# LPC1769.net
KiCad netlist of a schematic drawn in Altium Designer
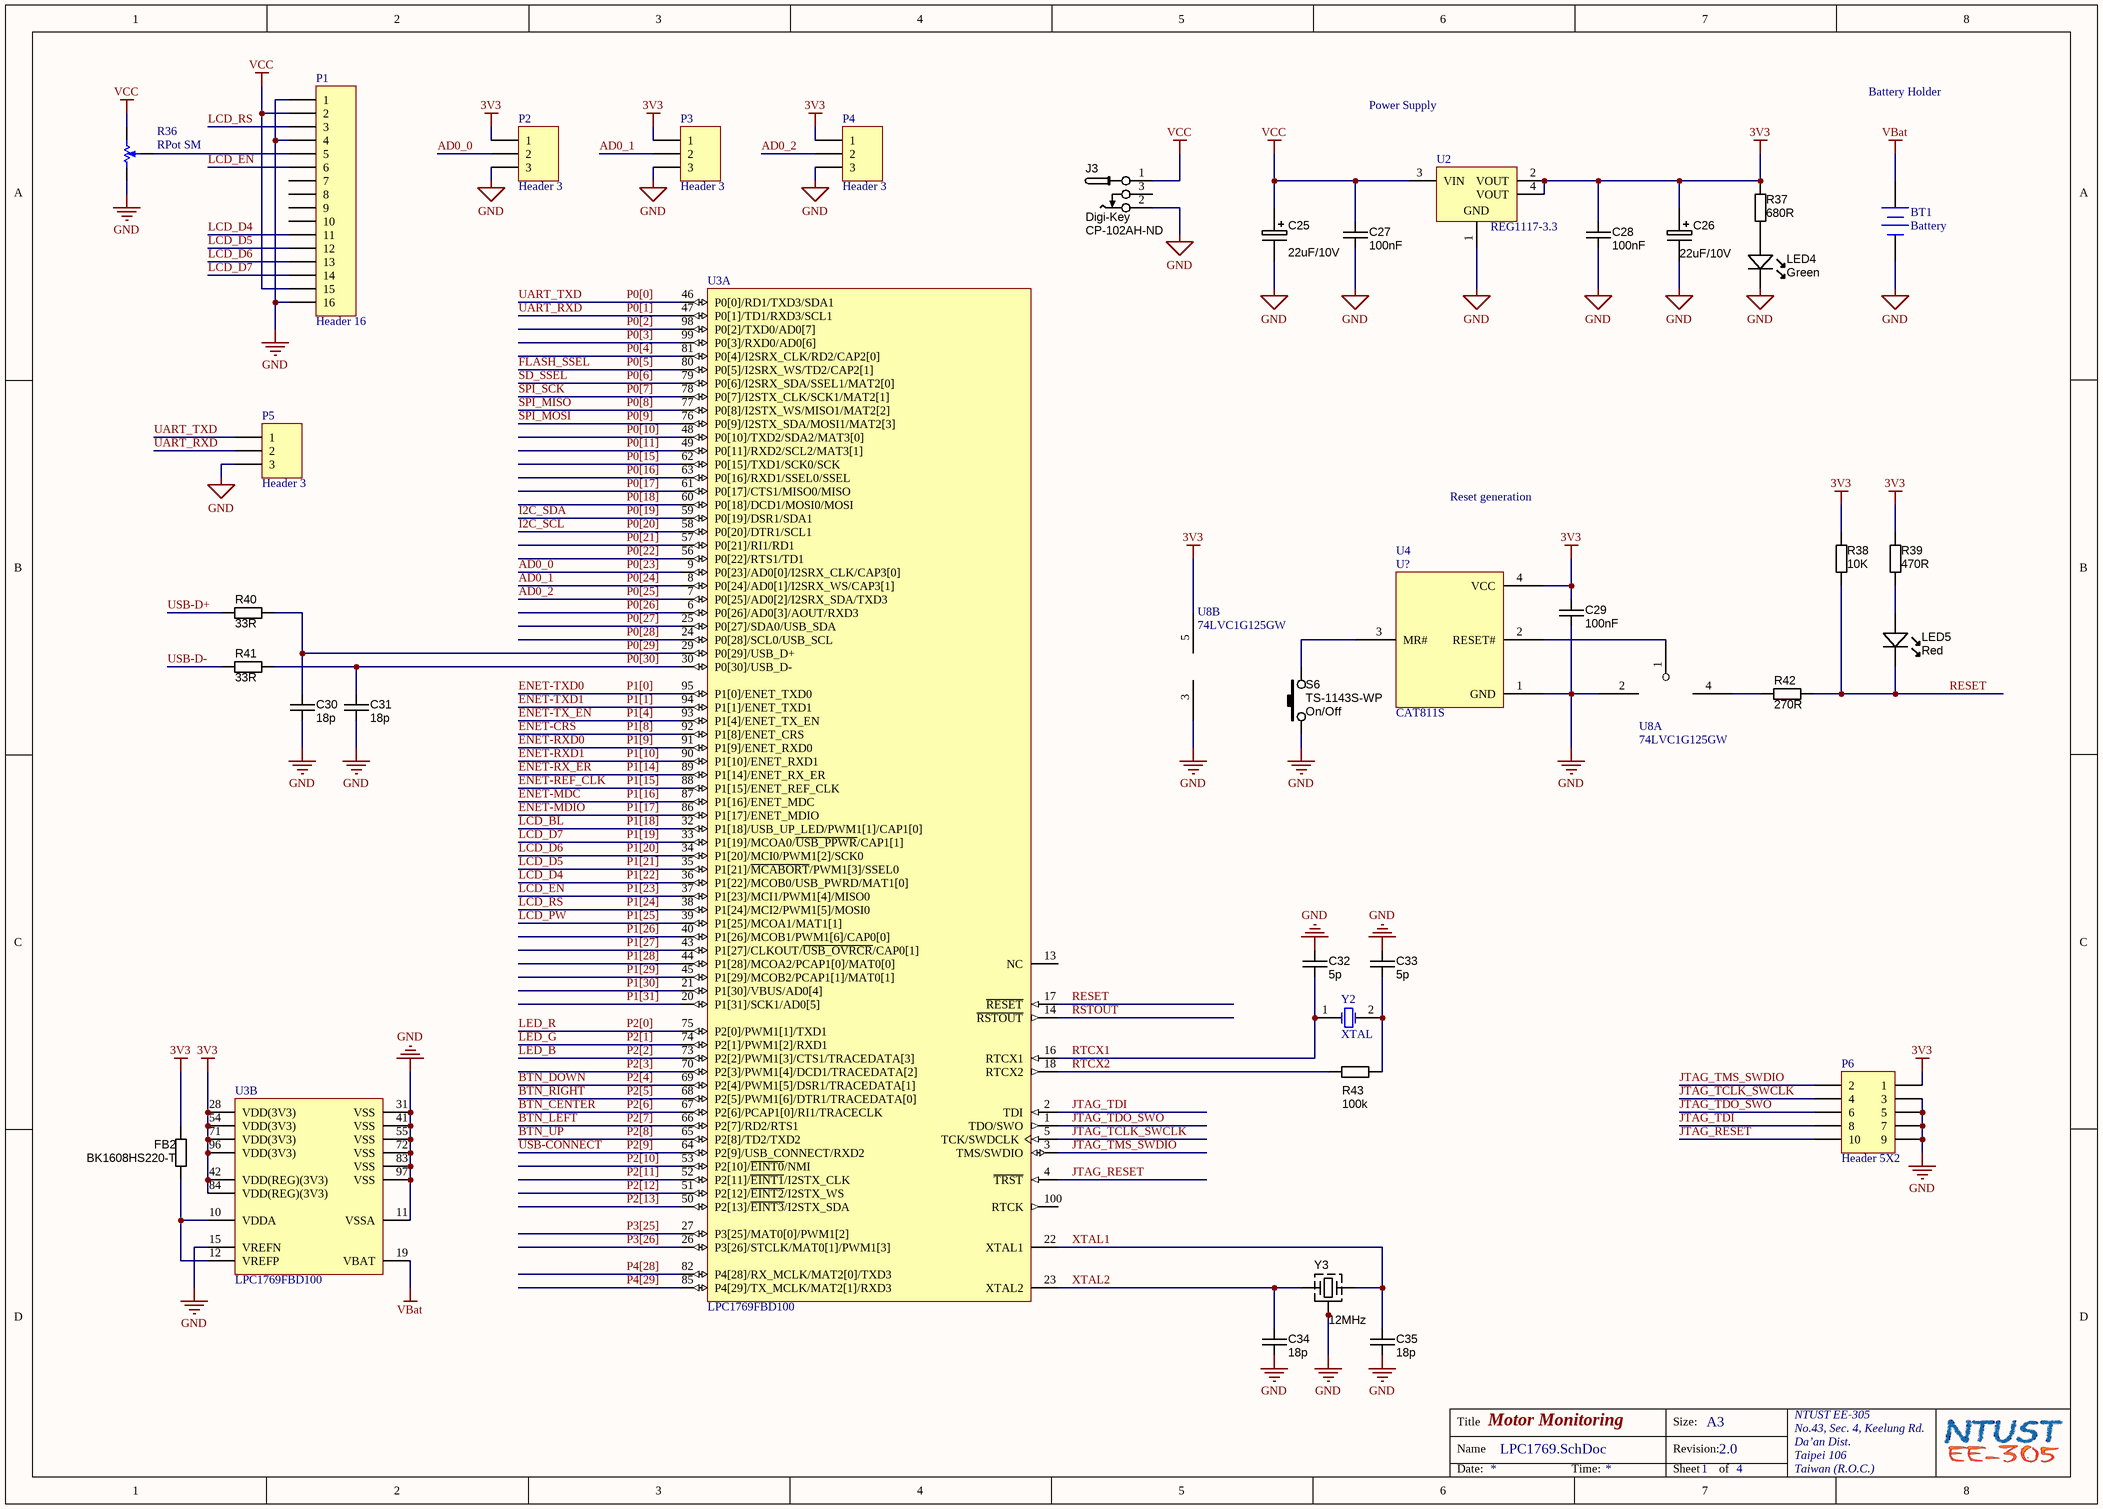
[diagram p0: LPC1769.SchDoc]

(export (version "E")
  (design (tool "Eeschema 10.0.6"))
  (components
    (comp (ref "BT1")
      (value "Battery")
      (footprint "BAT-2")
      (description "Multicell Battery")
      (fields (field (name "PUBLISHER") "Altium Limited"))
      (libsource (lib "Miscellaneous Devices") (part "Battery"))
    )
    (comp (ref "C25")
      (value "~")
      (footprint "CAP_ELEC_5x5.7")
      (description "Capacitor SMD Tantalum 100uF 20% 6.3V 1210")
      (fields (field (name "TOLERANCE") "?0%") (field (name "ALTIUM_UNNAMED_1") "22uF/10V"))
      (libsource (lib "PBL - Capacitors") (part "CAPT_100u_1210_6V3"))
    )
    (comp (ref "C26")
      (value "~")
      (footprint "CAP_ELEC_5x5.7")
      (description "Capacitor SMD Tantalum 100uF 20% 6.3V 1210")
      (fields (field (name "TOLERANCE") "?0%") (field (name "ALTIUM_UNNAMED_1") "22uF/10V"))
      (libsource (lib "PBL - Capacitors") (part "CAPT_100u_1210_6V3"))
    )
    (comp (ref "C27")
      (value "100nF")
      (footprint "CAPC1608N")
      (description "Capacitor SMD Cer 100nF 10% 50V X7R 0805")
      (fields (field (name "TOLERANCE") "?0%") (field (name "Comment") "approved sub OK"))
      (libsource (lib "PBL - Capacitors") (part "CAPC_100n_0805"))
    )
    (comp (ref "C28")
      (value "100nF")
      (footprint "CAPC1608N")
      (description "Capacitor SMD Cer 100nF 10% 50V X7R 0805")
      (fields (field (name "TOLERANCE") "?0%") (field (name "Comment") "approved sub OK"))
      (libsource (lib "PBL - Capacitors") (part "CAPC_100n_0805"))
    )
    (comp (ref "C29")
      (value "100nF")
      (footprint "CAPC1005N")
      (description "Capacitor SMD Cer 100nF 10% 50V X7R 0805")
      (fields (field (name "TOLERANCE") "?0%") (field (name "Comment") "approved sub OK"))
      (libsource (lib "PBL - Capacitors") (part "CAPC_100n_0805"))
    )
    (comp (ref "C30")
      (value "18p")
      (footprint "CAPC1608N")
      (description "Capacitor SMD Cer 100nF 10% 50V X7R 0805")
      (fields (field (name "TOLERANCE") "?0%") (field (name "Comment") "approved sub OK"))
      (libsource (lib "PBL - Capacitors") (part "CAPC_100n_0805"))
    )
    (comp (ref "C31")
      (value "18p")
      (footprint "CAPC1608N")
      (description "Capacitor SMD Cer 100nF 10% 50V X7R 0805")
      (fields (field (name "TOLERANCE") "?0%") (field (name "Comment") "approved sub OK"))
      (libsource (lib "PBL - Capacitors") (part "CAPC_100n_0805"))
    )
    (comp (ref "C32")
      (value "5p")
      (footprint "CAPC1005N")
      (description "Capacitor SMD Cer 100nF 10% 50V X7R 0805")
      (fields (field (name "TOLERANCE") "?0%") (field (name "Comment") "approved sub OK"))
      (libsource (lib "PBL - Capacitors") (part "CAPC_100n_0805"))
    )
    (comp (ref "C33")
      (value "5p")
      (footprint "CAPC1005N")
      (description "Capacitor SMD Cer 100nF 10% 50V X7R 0805")
      (fields (field (name "TOLERANCE") "?0%") (field (name "Comment") "approved sub OK"))
      (libsource (lib "PBL - Capacitors") (part "CAPC_100n_0805"))
    )
    (comp (ref "C34")
      (value "18p")
      (footprint "CAPC1005N")
      (description "Capacitor SMD Cer 100nF 10% 50V X7R 0805")
      (fields (field (name "TOLERANCE") "?0%") (field (name "Comment") "approved sub OK"))
      (libsource (lib "PBL - Capacitors") (part "CAPC_100n_0805"))
    )
    (comp (ref "C35")
      (value "18p")
      (footprint "CAPC1005N")
      (description "Capacitor SMD Cer 100nF 10% 50V X7R 0805")
      (fields (field (name "TOLERANCE") "?0%") (field (name "Comment") "approved sub OK"))
      (libsource (lib "PBL - Capacitors") (part "CAPC_100n_0805"))
    )
    (comp (ref "FB2")
      (value "BK1608HS220-T")
      (footprint "RESC2012N")
      (description "Resistor SMD chip 10k Ohm 0.125W 5% 0805")
      (fields (field (name "TOLERANCE") "?%") (field (name "Comment") "Thick Film"))
      (libsource (lib "") (part "RES_10K_0805_5%_1"))
    )
    (comp (ref "J3")
      (value "CONN_PWR_JACK_2.1x5.5mm")
      (footprint "CONN_PWR_JACK_2.1x5.5mm")
      (description "Power Connector, THT, 2.1mm ID, 5.5mm OD")
      (fields (field (name "SUPPLIER 1") "Digi-Key") (field (name "SUPPLIER PART NUMBER 1") "CP-102AH-ND"))
      (libsource (lib "PBL - Connectors") (part "CONN_PWR_JACK_2.1x5.5mm"))
    )
    (comp (ref "LED4")
      (value "Green")
      (footprint "LED-0603-GREEN")
      (description "LED, 0805 SMD, Green")
      (libsource (lib "PBL - Light Sources") (part "LED_SMD_Green_0805_8mcd"))
    )
    (comp (ref "LED5")
      (value "Red")
      (footprint "LED-0603-GREEN")
      (description "LED, 0805 SMD, Red")
      (libsource (lib "PBL - Light Sources") (part "LED_SMD_Red_0805"))
    )
    (comp (ref "P1")
      (value "Header 16")
      (footprint "HDR1X16")
      (description "Header, 16-Pin")
      (fields (field (name "PUBLISHER") "Altium Limited"))
      (libsource (lib "Miscellaneous Connectors") (part "Header 16"))
    )
    (comp (ref "P2")
      (value "Header 3")
      (footprint "HDR1X3")
      (description "Header, 3-Pin")
      (fields (field (name "PUBLISHER") "Altium Limited"))
      (libsource (lib "Miscellaneous Connectors") (part "Header 3"))
    )
    (comp (ref "P3")
      (value "Header 3")
      (footprint "HDR1X3")
      (description "Header, 3-Pin")
      (fields (field (name "PUBLISHER") "Altium Limited"))
      (libsource (lib "Miscellaneous Connectors") (part "Header 3"))
    )
    (comp (ref "P4")
      (value "Header 3")
      (footprint "HDR1X3")
      (description "Header, 3-Pin")
      (fields (field (name "PUBLISHER") "Altium Limited"))
      (libsource (lib "Miscellaneous Connectors") (part "Header 3"))
    )
    (comp (ref "P5")
      (value "Header 3")
      (footprint "HDR1X3")
      (description "Header, 3-Pin")
      (fields (field (name "PUBLISHER") "Altium Limited"))
      (libsource (lib "Miscellaneous Connectors") (part "Header 3"))
    )
    (comp (ref "P6")
      (value "Header 5X2")
      (footprint "Header 5x2p")
      (description "Header, 5-Pin, Dual row")
      (fields (field (name "PUBLISHER") "Altium Limited"))
      (libsource (lib "Miscellaneous Connectors") (part "Header 5X2"))
    )
    (comp (ref "R36")
      (value "RPot SM")
      (footprint "POT4MM-2")
      (description "Square Trimming Potentiometer")
      (fields (field (name "PUBLISHER") "Altium Limited"))
      (libsource (lib "Miscellaneous Devices") (part "RPot SM"))
    )
    (comp (ref "R37")
      (value "680R")
      (footprint "RESC1005N")
      (description "Resistor SMD chip 330 Ohm 0.063W 5% 0402")
      (fields (field (name "TOLERANCE") "?%") (field (name "Comment") "Thick Film"))
      (libsource (lib "") (part "RES_330R_0402_5%_1"))
    )
    (comp (ref "R38")
      (value "10K")
      (footprint "RESC1005N")
      (description "Resistor SMD chip 10k Ohm 0.125W 5% 0805")
      (fields (field (name "TOLERANCE") "?%") (field (name "Comment") "Thick Film"))
      (libsource (lib "") (part "RES_10K_0805_5%_1"))
    )
    (comp (ref "R39")
      (value "470R")
      (footprint "RESC1005N")
      (description "Resistor SMD chip 470 Ohm 0.1W 5% 0603")
      (fields (field (name "TOLERANCE") "?%") (field (name "Comment") "Thick Film"))
      (libsource (lib "PBL - Resistors") (part "RES_470R_0603_5%"))
    )
    (comp (ref "R40")
      (value "33R")
      (footprint "RESC1608N")
      (description "Resistor SMD chip 10k Ohm 0.125W 5% 0805")
      (fields (field (name "TOLERANCE") "?%") (field (name "Comment") "Thick Film"))
      (libsource (lib "PBL - Resistors") (part "RES_10K_0805_5%"))
    )
    (comp (ref "R41")
      (value "33R")
      (footprint "RESC1608N")
      (description "Resistor SMD chip 10k Ohm 0.125W 5% 0805")
      (fields (field (name "TOLERANCE") "?%") (field (name "Comment") "Thick Film"))
      (libsource (lib "PBL - Resistors") (part "RES_10K_0805_5%"))
    )
    (comp (ref "R42")
      (value "270R")
      (footprint "RESC1005N")
      (description "Resistor SMD chip 330 Ohm 0.063W 5% 0402")
      (fields (field (name "TOLERANCE") "?%") (field (name "Comment") "Thick Film"))
      (libsource (lib "PBL - Resistors") (part "RES_330R_0402_5%"))
    )
    (comp (ref "R43")
      (value "100k")
      (footprint "RESC1005N")
      (description "Resistor SMD chip 10k Ohm 0.125W 5% 0805")
      (fields (field (name "TOLERANCE") "?%") (field (name "Comment") "Thick Film"))
      (libsource (lib "PBL - Resistors") (part "RES_10K_0805_5%"))
    )
    (comp (ref "S6")
      (value "TS-1143S-WP")
      (footprint "TS-1143S")
      (description "Switch SMD Tact 4.3mm Stem")
      (fields (field (name "FUNCTION") "On/Off"))
      (libsource (lib "PBL - Switches") (part "SW_SMD_PB_4.3mm"))
    )
    (comp (ref "U2")
      (value "REG1117-3.3")
      (footprint "TI-DCY4_N")
      (fields (field (name "MANUFACTURER") "Texas Instruments"))
      (libsource (lib "TI Power Management Linear Regulator Single Channel LDO (400-7500mA)") (part "REG1117-3.3"))
    )
    (comp (ref "U3")
      (value "LPC1769FBD100")
      (footprint "SOT407-1_V")
      (libsource (lib "NXP Semiconductors Cortex-M3") (part "LPC1769FBD100"))
    )
    (comp (ref "U4")
      (value "CAT811S")
      (footprint "SOT-143-RC4_N")
      (libsource (lib "Schlib1") (part "CAT811S"))
    )
    (comp (ref "U8")
      (value "74LVC1G125GW")
      (footprint "SOT-23-CT5_N")
      (libsource (lib "Schlib1") (part "74LVC1G125GW"))
    )
    (comp (ref "Y2")
      (value "XTAL")
      (footprint "HC49/4H_SMX")
      (description "Crystal Oscillator")
      (fields (field (name "PUBLISHER") "Altium Limited"))
      (libsource (lib "Miscellaneous Devices") (part "XTAL"))
    )
    (comp (ref "Y3")
      (value "12MHz")
      (footprint "CRYSTAL_4-LCC")
      (description "Oscillator Crystal 27.12 MHz 10ppm")
      (libsource (lib "PBL - Resonators") (part "CRYSTAL_27M12"))
    )
  )
  (nets
    (net (code "1") (name "/AD0_0") (class "Default")
      (node (ref "P2") (pin "2") (pinfunction "2_2") (pintype "passive"))
      (node (ref "U3") (pin "9") (pinfunction "P0[23]/AD0[0]/I2SRX_CLK/CAP3[0]_9") (pintype "bidirectional"))
    )
    (net (code "2") (name "/AD0_1") (class "Default")
      (node (ref "P3") (pin "2") (pinfunction "2_2") (pintype "passive"))
      (node (ref "U3") (pin "8") (pinfunction "P0[24]/AD0[1]/I2SRX_WS/CAP3[1]_8") (pintype "bidirectional"))
    )
    (net (code "3") (name "/AD0_2") (class "Default")
      (node (ref "P4") (pin "2") (pinfunction "2_2") (pintype "passive"))
      (node (ref "U3") (pin "7") (pinfunction "P0[25]/AD0[2]/I2SRX_SDA/TXD3_7") (pintype "bidirectional"))
    )
    (net (code "4") (name "/BTN_CENTER") (class "Default")
      (node (ref "U3") (pin "67") (pinfunction "P2[6]/PCAP1[0]/RI1/TRACECLK_67") (pintype "bidirectional"))
    )
    (net (code "5") (name "/BTN_DOWN") (class "Default")
      (node (ref "U3") (pin "69") (pinfunction "P2[4]/PWM1[5]/DSR1/TRACEDATA[1]_69") (pintype "bidirectional"))
    )
    (net (code "6") (name "/BTN_LEFT") (class "Default")
      (node (ref "U3") (pin "66") (pinfunction "P2[7]/RD2/RTS1_66") (pintype "bidirectional"))
    )
    (net (code "7") (name "/BTN_RIGHT") (class "Default")
      (node (ref "U3") (pin "68") (pinfunction "P2[5]/PWM1[6]/DTR1/TRACEDATA[0]_68") (pintype "bidirectional"))
    )
    (net (code "8") (name "/BTN_UP") (class "Default")
      (node (ref "U3") (pin "65") (pinfunction "P2[8]/TD2/TXD2_65") (pintype "bidirectional"))
    )
    (net (code "9") (name "/ENET-CRS") (class "Default")
      (node (ref "U3") (pin "92") (pinfunction "P1[8]/ENET_CRS_92") (pintype "bidirectional"))
    )
    (net (code "10") (name "/ENET-MDC") (class "Default")
      (node (ref "U3") (pin "87") (pinfunction "P1[16]/ENET_MDC_87") (pintype "bidirectional"))
    )
    (net (code "11") (name "/ENET-MDIO") (class "Default")
      (node (ref "U3") (pin "86") (pinfunction "P1[17]/ENET_MDIO_86") (pintype "bidirectional"))
    )
    (net (code "12") (name "/ENET-REF_CLK") (class "Default")
      (node (ref "U3") (pin "88") (pinfunction "P1[15]/ENET_REF_CLK_88") (pintype "bidirectional"))
    )
    (net (code "13") (name "/ENET-RXD0") (class "Default")
      (node (ref "U3") (pin "91") (pinfunction "P1[9]/ENET_RXD0_91") (pintype "bidirectional"))
    )
    (net (code "14") (name "/ENET-RXD1") (class "Default")
      (node (ref "U3") (pin "90") (pinfunction "P1[10]/ENET_RXD1_90") (pintype "bidirectional"))
    )
    (net (code "15") (name "/ENET-RX_ER") (class "Default")
      (node (ref "U3") (pin "89") (pinfunction "P1[14]/ENET_RX_ER_89") (pintype "bidirectional"))
    )
    (net (code "16") (name "/ENET-TXD0") (class "Default")
      (node (ref "U3") (pin "95") (pinfunction "P1[0]/ENET_TXD0_95") (pintype "bidirectional"))
    )
    (net (code "17") (name "/ENET-TXD1") (class "Default")
      (node (ref "U3") (pin "94") (pinfunction "P1[1]/ENET_TXD1_94") (pintype "bidirectional"))
    )
    (net (code "18") (name "/ENET-TX_EN") (class "Default")
      (node (ref "U3") (pin "93") (pinfunction "P1[4]/ENET_TX_EN_93") (pintype "bidirectional"))
    )
    (net (code "19") (name "/FLASH_SSEL") (class "Default")
      (node (ref "U3") (pin "80") (pinfunction "P0[5]/I2SRX_WS/TD2/CAP2[1]_80") (pintype "bidirectional"))
    )
    (net (code "20") (name "/I2C_SCL") (class "Default")
      (node (ref "U3") (pin "58") (pinfunction "P0[20]/DTR1/SCL1_58") (pintype "bidirectional"))
    )
    (net (code "21") (name "/I2C_SDA") (class "Default")
      (node (ref "U3") (pin "59") (pinfunction "P0[19]/DSR1/SDA1_59") (pintype "bidirectional"))
    )
    (net (code "22") (name "/JTAG_RESET") (class "Default")
      (node (ref "P6") (pin "10") (pinfunction "10_10") (pintype "passive"))
      (node (ref "U3") (pin "4") (pinfunction "~{TRST}_4") (pintype "input"))
    )
    (net (code "23") (name "/JTAG_TCLK_SWCLK") (class "Default")
      (node (ref "P6") (pin "4") (pinfunction "4_4") (pintype "passive"))
      (node (ref "U3") (pin "5") (pinfunction "TCK/SWDCLK_5") (pintype "input"))
    )
    (net (code "24") (name "/JTAG_TDI") (class "Default")
      (node (ref "P6") (pin "8") (pinfunction "8_8") (pintype "passive"))
      (node (ref "U3") (pin "2") (pinfunction "TDI_2") (pintype "input"))
    )
    (net (code "25") (name "/JTAG_TDO_SWO") (class "Default")
      (node (ref "P6") (pin "6") (pinfunction "6_6") (pintype "passive"))
      (node (ref "U3") (pin "1") (pinfunction "TDO/SWO_1") (pintype "output"))
    )
    (net (code "26") (name "/JTAG_TMS_SWDIO") (class "Default")
      (node (ref "P6") (pin "2") (pinfunction "2_2") (pintype "passive"))
      (node (ref "U3") (pin "3") (pinfunction "TMS/SWDIO_3") (pintype "bidirectional"))
    )
    (net (code "27") (name "/LCD_BL") (class "Default")
      (node (ref "U3") (pin "32") (pinfunction "P1[18]/USB_UP_LED/PWM1[1]/CAP1[0]_32") (pintype "bidirectional"))
    )
    (net (code "28") (name "/LCD_D4") (class "Default")
      (node (ref "P1") (pin "11") (pinfunction "11_11") (pintype "passive"))
      (node (ref "U3") (pin "36") (pinfunction "P1[22]/MCOB0/USB_PWRD/MAT1[0]_36") (pintype "bidirectional"))
    )
    (net (code "29") (name "/LCD_D5") (class "Default")
      (node (ref "P1") (pin "12") (pinfunction "12_12") (pintype "passive"))
      (node (ref "U3") (pin "35") (pinfunction "P1[21]/~{MCABORT}/PWM1[3]/SSEL0_35") (pintype "bidirectional"))
    )
    (net (code "30") (name "/LCD_D6") (class "Default")
      (node (ref "P1") (pin "13") (pinfunction "13_13") (pintype "passive"))
      (node (ref "U3") (pin "34") (pinfunction "P1[20]/MCI0/PWM1[2]/SCK0_34") (pintype "bidirectional"))
    )
    (net (code "31") (name "/LCD_D7") (class "Default")
      (node (ref "P1") (pin "14") (pinfunction "14_14") (pintype "passive"))
      (node (ref "U3") (pin "33") (pinfunction "P1[19]/MCOA0/~{USB_PPWR}/CAP1[1]_33") (pintype "bidirectional"))
    )
    (net (code "32") (name "/LCD_EN") (class "Default")
      (node (ref "P1") (pin "6") (pinfunction "6_6") (pintype "passive"))
      (node (ref "U3") (pin "37") (pinfunction "P1[23]/MCI1/PWM1[4]/MISO0_37") (pintype "bidirectional"))
    )
    (net (code "33") (name "/LCD_PW") (class "Default")
      (node (ref "U3") (pin "39") (pinfunction "P1[25]/MCOA1/MAT1[1]_39") (pintype "bidirectional"))
    )
    (net (code "34") (name "/LCD_RS") (class "Default")
      (node (ref "P1") (pin "3") (pinfunction "3_3") (pintype "passive"))
      (node (ref "U3") (pin "38") (pinfunction "P1[24]/MCI2/PWM1[5]/MOSI0_38") (pintype "bidirectional"))
    )
    (net (code "35") (name "/LED_B") (class "Default")
      (node (ref "U3") (pin "73") (pinfunction "P2[2]/PWM1[3]/CTS1/TRACEDATA[3]_73") (pintype "bidirectional"))
    )
    (net (code "36") (name "/LED_G") (class "Default")
      (node (ref "U3") (pin "74") (pinfunction "P2[1]/PWM1[2]/RXD1_74") (pintype "bidirectional"))
    )
    (net (code "37") (name "/LED_R") (class "Default")
      (node (ref "U3") (pin "75") (pinfunction "P2[0]/PWM1[1]/TXD1_75") (pintype "bidirectional"))
    )
    (net (code "38") (name "/P0[0]") (class "Default")
      (node (ref "P5") (pin "1") (pinfunction "1_1") (pintype "passive"))
      (node (ref "U3") (pin "46") (pinfunction "P0[0]/RD1/TXD3/SDA1_46") (pintype "bidirectional"))
    )
    (net (code "39") (name "/P0[1]") (class "Default")
      (node (ref "P5") (pin "2") (pinfunction "2_2") (pintype "passive"))
      (node (ref "U3") (pin "47") (pinfunction "P0[1]/TD1/RXD3/SCL1_47") (pintype "bidirectional"))
    )
    (net (code "40") (name "/P0[2]") (class "Default")
      (node (ref "U3") (pin "98") (pinfunction "P0[2]/TXD0/AD0[7]_98") (pintype "bidirectional"))
    )
    (net (code "41") (name "/P0[3]") (class "Default")
      (node (ref "U3") (pin "99") (pinfunction "P0[3]/RXD0/AD0[6]_99") (pintype "bidirectional"))
    )
    (net (code "42") (name "/P0[4]") (class "Default")
      (node (ref "U3") (pin "81") (pinfunction "P0[4]/I2SRX_CLK/RD2/CAP2[0]_81") (pintype "bidirectional"))
    )
    (net (code "43") (name "/P0[6]") (class "Default")
      (node (ref "U3") (pin "79") (pinfunction "P0[6]/I2SRX_SDA/SSEL1/MAT2[0]_79") (pintype "bidirectional"))
    )
    (net (code "44") (name "/P0[7]") (class "Default")
      (node (ref "U3") (pin "78") (pinfunction "P0[7]/I2STX_CLK/SCK1/MAT2[1]_78") (pintype "bidirectional"))
    )
    (net (code "45") (name "/P0[8]") (class "Default")
      (node (ref "U3") (pin "77") (pinfunction "P0[8]/I2STX_WS/MISO1/MAT2[2]_77") (pintype "bidirectional"))
    )
    (net (code "46") (name "/P0[9]") (class "Default")
      (node (ref "U3") (pin "76") (pinfunction "P0[9]/I2STX_SDA/MOSI1/MAT2[3]_76") (pintype "bidirectional"))
    )
    (net (code "47") (name "/P0[10]") (class "Default")
      (node (ref "U3") (pin "48") (pinfunction "P0[10]/TXD2/SDA2/MAT3[0]_48") (pintype "bidirectional"))
    )
    (net (code "48") (name "/P0[11]") (class "Default")
      (node (ref "U3") (pin "49") (pinfunction "P0[11]/RXD2/SCL2/MAT3[1]_49") (pintype "bidirectional"))
    )
    (net (code "49") (name "/P0[15]") (class "Default")
      (node (ref "U3") (pin "62") (pinfunction "P0[15]/TXD1/SCK0/SCK_62") (pintype "bidirectional"))
    )
    (net (code "50") (name "/P0[16]") (class "Default")
      (node (ref "U3") (pin "63") (pinfunction "P0[16]/RXD1/SSEL0/SSEL_63") (pintype "bidirectional"))
    )
    (net (code "51") (name "/P0[17]") (class "Default")
      (node (ref "U3") (pin "61") (pinfunction "P0[17]/CTS1/MISO0/MISO_61") (pintype "bidirectional"))
    )
    (net (code "52") (name "/P0[18]") (class "Default")
      (node (ref "U3") (pin "60") (pinfunction "P0[18]/DCD1/MOSI0/MOSI_60") (pintype "bidirectional"))
    )
    (net (code "53") (name "/P0[21]") (class "Default")
      (node (ref "U3") (pin "57") (pinfunction "P0[21]/RI1/RD1_57") (pintype "bidirectional"))
    )
    (net (code "54") (name "/P0[22]") (class "Default")
      (node (ref "U3") (pin "56") (pinfunction "P0[22]/RTS1/TD1_56") (pintype "bidirectional"))
    )
    (net (code "55") (name "/P0[26]") (class "Default")
      (node (ref "U3") (pin "6") (pinfunction "P0[26]/AD0[3]/AOUT/RXD3_6") (pintype "bidirectional"))
    )
    (net (code "56") (name "/P0[27]") (class "Default")
      (node (ref "U3") (pin "25") (pinfunction "P0[27]/SDA0/USB_SDA_25") (pintype "bidirectional"))
    )
    (net (code "57") (name "/P0[28]") (class "Default")
      (node (ref "U3") (pin "24") (pinfunction "P0[28]/SCL0/USB_SCL_24") (pintype "bidirectional"))
    )
    (net (code "58") (name "/P0[29]") (class "Default")
      (node (ref "C30") (pin "2") (pintype "passive"))
      (node (ref "R40") (pin "1") (pinfunction "1_1") (pintype "passive"))
      (node (ref "U3") (pin "29") (pinfunction "P0[29]/USB_D+_29") (pintype "bidirectional"))
    )
    (net (code "59") (name "/P0[30]") (class "Default")
      (node (ref "C31") (pin "2") (pintype "passive"))
      (node (ref "R41") (pin "1") (pinfunction "1_1") (pintype "passive"))
      (node (ref "U3") (pin "30") (pinfunction "P0[30]/USB_D-_30") (pintype "bidirectional"))
    )
    (net (code "60") (name "/P1[26]") (class "Default")
      (node (ref "U3") (pin "40") (pinfunction "P1[26]/MCOB1/PWM1[6]/CAP0[0]_40") (pintype "bidirectional"))
    )
    (net (code "61") (name "/P1[27]") (class "Default")
      (node (ref "U3") (pin "43") (pinfunction "P1[27]/CLKOUT/~{USB_OVRCR}/CAP0[1]_43") (pintype "bidirectional"))
    )
    (net (code "62") (name "/P1[28]") (class "Default")
      (node (ref "U3") (pin "44") (pinfunction "P1[28]/MCOA2/PCAP1[0]/MAT0[0]_44") (pintype "bidirectional"))
    )
    (net (code "63") (name "/P1[29]") (class "Default")
      (node (ref "U3") (pin "45") (pinfunction "P1[29]/MCOB2/PCAP1[1]/MAT0[1]_45") (pintype "bidirectional"))
    )
    (net (code "64") (name "/P1[30]") (class "Default")
      (node (ref "U3") (pin "21") (pinfunction "P1[30]/VBUS/AD0[4]_21") (pintype "bidirectional"))
    )
    (net (code "65") (name "/P1[31]") (class "Default")
      (node (ref "U3") (pin "20") (pinfunction "P1[31]/SCK1/AD0[5]_20") (pintype "bidirectional"))
    )
    (net (code "66") (name "/P2[3]") (class "Default")
      (node (ref "U3") (pin "70") (pinfunction "P2[3]/PWM1[4]/DCD1/TRACEDATA[2]_70") (pintype "bidirectional"))
    )
    (net (code "67") (name "/P2[9]") (class "Default")
      (node (ref "U3") (pin "64") (pinfunction "P2[9]/USB_CONNECT/RXD2_64") (pintype "bidirectional"))
    )
    (net (code "68") (name "/P2[10]") (class "Default")
      (node (ref "U3") (pin "53") (pinfunction "P2[10]/~{EINT0}/NMI_53") (pintype "bidirectional"))
    )
    (net (code "69") (name "/P2[11]") (class "Default")
      (node (ref "U3") (pin "52") (pinfunction "P2[11]/~{EINT1}/I2STX_CLK_52") (pintype "bidirectional"))
    )
    (net (code "70") (name "/P2[12]") (class "Default")
      (node (ref "U3") (pin "51") (pinfunction "P2[12]/~{EINT2}/I2STX_WS_51") (pintype "bidirectional"))
    )
    (net (code "71") (name "/P2[13]") (class "Default")
      (node (ref "U3") (pin "50") (pinfunction "P2[13]/~{EINT3}/I2STX_SDA_50") (pintype "bidirectional"))
    )
    (net (code "72") (name "/P3[25]") (class "Default")
      (node (ref "U3") (pin "27") (pinfunction "P3[25]/MAT0[0]/PWM1[2]_27") (pintype "bidirectional"))
    )
    (net (code "73") (name "/P3[26]") (class "Default")
      (node (ref "U3") (pin "26") (pinfunction "P3[26]/STCLK/MAT0[1]/PWM1[3]_26") (pintype "bidirectional"))
    )
    (net (code "74") (name "/P4[28]") (class "Default")
      (node (ref "U3") (pin "82") (pinfunction "P4[28]/RX_MCLK/MAT2[0]/TXD3_82") (pintype "bidirectional"))
    )
    (net (code "75") (name "/P4[29]") (class "Default")
      (node (ref "U3") (pin "85") (pinfunction "P4[29]/TX_MCLK/MAT2[1]/RXD3_85") (pintype "bidirectional"))
    )
    (net (code "76") (name "/RESET") (class "Default")
      (node (ref "LED5") (pin "K") (pinfunction "K_K") (pintype "passive"))
      (node (ref "R38") (pin "1") (pinfunction "1_1") (pintype "passive"))
      (node (ref "R42") (pin "1") (pinfunction "1_1") (pintype "passive"))
      (node (ref "U3") (pin "17") (pinfunction "~{RESET}_17") (pintype "input"))
    )
    (net (code "77") (name "/RSTOUT") (class "Default")
      (node (ref "U3") (pin "14") (pinfunction "~{RSTOUT}_14") (pintype "output"))
    )
    (net (code "78") (name "/RTCX1") (class "Default")
      (node (ref "C32") (pin "1") (pintype "passive"))
      (node (ref "U3") (pin "16") (pinfunction "RTCX1_16") (pintype "input"))
      (node (ref "Y2") (pin "1") (pinfunction "OSC1_1") (pintype "passive"))
    )
    (net (code "79") (name "/RTCX2") (class "Default")
      (node (ref "R43") (pin "2") (pinfunction "2_2") (pintype "passive"))
      (node (ref "U3") (pin "18") (pinfunction "RTCX2_18") (pintype "output"))
    )
    (net (code "80") (name "/USB-D+") (class "Default")
      (node (ref "R40") (pin "2") (pinfunction "2_2") (pintype "passive"))
    )
    (net (code "81") (name "/USB-D-") (class "Default")
      (node (ref "R41") (pin "2") (pinfunction "2_2") (pintype "passive"))
    )
    (net (code "82") (name "/XTAL1") (class "Default")
      (node (ref "C35") (pin "2") (pintype "passive"))
      (node (ref "U3") (pin "22") (pinfunction "XTAL1_22") (pintype "passive"))
      (node (ref "Y3") (pin "3") (pinfunction "X_3") (pintype "passive"))
    )
    (net (code "83") (name "/XTAL2") (class "Default")
      (node (ref "C34") (pin "2") (pintype "passive"))
      (node (ref "U3") (pin "23") (pinfunction "XTAL2_23") (pintype "passive"))
      (node (ref "Y3") (pin "1") (pinfunction "X_1") (pintype "passive"))
    )
    (net (code "84") (name "3V3") (class "Default")
      (node (ref "C26") (pin "1") (pintype "passive"))
      (node (ref "C28") (pin "2") (pintype "passive"))
      (node (ref "C29") (pin "1") (pintype "passive"))
      (node (ref "FB2") (pin "2") (pinfunction "2_2") (pintype "passive"))
      (node (ref "P2") (pin "1") (pinfunction "1_1") (pintype "passive"))
      (node (ref "P3") (pin "1") (pinfunction "1_1") (pintype "passive"))
      (node (ref "P4") (pin "1") (pinfunction "1_1") (pintype "passive"))
      (node (ref "P6") (pin "1") (pinfunction "1_1") (pintype "passive"))
      (node (ref "R37") (pin "2") (pinfunction "2_2") (pintype "passive"))
      (node (ref "R38") (pin "2") (pinfunction "2_2") (pintype "passive"))
      (node (ref "R39") (pin "2") (pinfunction "2_2") (pintype "passive"))
      (node (ref "U2") (pin "2") (pinfunction "VOUT_2") (pintype "power_in"))
      (node (ref "U2") (pin "4") (pinfunction "VOUT_4") (pintype "power_in"))
      (node (ref "U3") (pin "28") (pinfunction "VDD(3V3)_28") (pintype "power_in"))
      (node (ref "U3") (pin "42") (pinfunction "VDD(REG)(3V3)_42") (pintype "power_in"))
      (node (ref "U3") (pin "54") (pinfunction "VDD(3V3)_54") (pintype "power_in"))
      (node (ref "U3") (pin "71") (pinfunction "VDD(3V3)_71") (pintype "power_in"))
      (node (ref "U3") (pin "84") (pinfunction "VDD(REG)(3V3)_84") (pintype "power_in"))
      (node (ref "U3") (pin "96") (pinfunction "VDD(3V3)_96") (pintype "power_in"))
      (node (ref "U4") (pin "4") (pinfunction "VCC_4") (pintype "passive"))
      (node (ref "U8") (pin "5") (pinfunction "VCC_5") (pintype "passive"))
    )
    (net (code "85") (name "GND") (class "Default")
      (node (ref "BT1") (pin "2") (pinfunction "-_2") (pintype "passive"))
      (node (ref "C25") (pin "2") (pintype "passive"))
      (node (ref "C26") (pin "2") (pintype "passive"))
      (node (ref "C27") (pin "2") (pintype "passive"))
      (node (ref "C28") (pin "1") (pintype "passive"))
      (node (ref "C29") (pin "2") (pintype "passive"))
      (node (ref "C30") (pin "1") (pintype "passive"))
      (node (ref "C31") (pin "1") (pintype "passive"))
      (node (ref "C32") (pin "2") (pintype "passive"))
      (node (ref "C33") (pin "2") (pintype "passive"))
      (node (ref "C34") (pin "1") (pintype "passive"))
      (node (ref "C35") (pin "1") (pintype "passive"))
      (node (ref "J3") (pin "2") (pinfunction "2_2") (pintype "passive"))
      (node (ref "LED4") (pin "K") (pinfunction "K_K") (pintype "passive"))
      (node (ref "P1") (pin "1") (pinfunction "1_1") (pintype "passive"))
      (node (ref "P1") (pin "16") (pinfunction "16_16") (pintype "passive"))
      (node (ref "P1") (pin "4") (pinfunction "4_4") (pintype "passive"))
      (node (ref "P2") (pin "3") (pinfunction "3_3") (pintype "passive"))
      (node (ref "P3") (pin "3") (pinfunction "3_3") (pintype "passive"))
      (node (ref "P4") (pin "3") (pinfunction "3_3") (pintype "passive"))
      (node (ref "P5") (pin "3") (pinfunction "3_3") (pintype "passive"))
      (node (ref "P6") (pin "3") (pinfunction "3_3") (pintype "passive"))
      (node (ref "P6") (pin "5") (pinfunction "5_5") (pintype "passive"))
      (node (ref "P6") (pin "7") (pinfunction "7_7") (pintype "passive"))
      (node (ref "P6") (pin "9") (pinfunction "9_9") (pintype "passive"))
      (node (ref "R36") (pin "CCW") (pinfunction "-_CCW") (pintype "passive"))
      (node (ref "S6") (pin "1") (pintype "passive"))
      (node (ref "U2") (pin "1") (pinfunction "GND_1") (pintype "power_in"))
      (node (ref "U3") (pin "11") (pinfunction "VSSA_11") (pintype "power_in"))
      (node (ref "U3") (pin "15") (pinfunction "VREFN_15") (pintype "power_in"))
      (node (ref "U3") (pin "31") (pinfunction "VSS_31") (pintype "power_in"))
      (node (ref "U3") (pin "41") (pinfunction "VSS_41") (pintype "power_in"))
      (node (ref "U3") (pin "55") (pinfunction "VSS_55") (pintype "power_in"))
      (node (ref "U3") (pin "72") (pinfunction "VSS_72") (pintype "power_in"))
      (node (ref "U3") (pin "83") (pinfunction "VSS_83") (pintype "power_in"))
      (node (ref "U3") (pin "97") (pinfunction "VSS_97") (pintype "power_in"))
      (node (ref "U4") (pin "1") (pinfunction "GND_1") (pintype "passive"))
      (node (ref "U8") (pin "2") (pinfunction "A_2") (pintype "passive"))
      (node (ref "U8") (pin "3") (pinfunction "GND_3") (pintype "passive"))
      (node (ref "Y3") (pin "2") (pinfunction "GND_2") (pintype "passive"))
      (node (ref "Y3") (pin "4") (pinfunction "GND_4") (pintype "passive"))
    )
    (net (code "86") (name "Net-(LED4-PadA)") (class "Default")
      (node (ref "LED4") (pin "A") (pinfunction "A_A") (pintype "passive"))
      (node (ref "R37") (pin "1") (pinfunction "1_1") (pintype "passive"))
    )
    (net (code "87") (name "Net-(LED5-PadA)") (class "Default")
      (node (ref "LED5") (pin "A") (pinfunction "A_A") (pintype "passive"))
      (node (ref "R39") (pin "1") (pinfunction "1_1") (pintype "passive"))
    )
    (net (code "88") (name "Net-(P1-Pad5)") (class "Default")
      (node (ref "P1") (pin "5") (pinfunction "5_5") (pintype "passive"))
      (node (ref "R36") (pin "W") (pinfunction "W_W") (pintype "passive"))
    )
    (net (code "89") (name "Net-(U3B-VDDA)") (class "Default")
      (node (ref "FB2") (pin "1") (pinfunction "1_1") (pintype "passive"))
      (node (ref "U3") (pin "10") (pinfunction "VDDA_10") (pintype "power_in"))
      (node (ref "U3") (pin "12") (pinfunction "VREFP_12") (pintype "power_in"))
    )
    (net (code "90") (name "Net-(U4-MR#)") (class "Default")
      (node (ref "S6") (pin "2") (pintype "passive"))
      (node (ref "U4") (pin "3") (pinfunction "MR#_3") (pintype "passive"))
    )
    (net (code "91") (name "Net-(U4-RESET#)") (class "Default")
      (node (ref "U4") (pin "2") (pinfunction "RESET#_2") (pintype "passive"))
      (node (ref "U8") (pin "1") (pinfunction "~{OE}_1") (pintype "passive"))
    )
    (net (code "92") (name "Net-(U8A-Y)") (class "Default")
      (node (ref "R42") (pin "2") (pinfunction "2_2") (pintype "passive"))
      (node (ref "U8") (pin "4") (pinfunction "Y_4") (pintype "passive"))
    )
    (net (code "93") (name "Net-(Y2-OSC2)") (class "Default")
      (node (ref "C33") (pin "1") (pintype "passive"))
      (node (ref "R43") (pin "1") (pinfunction "1_1") (pintype "passive"))
      (node (ref "Y2") (pin "2") (pinfunction "OSC2_2") (pintype "passive"))
    )
    (net (code "94") (name "VBat") (class "Default")
      (node (ref "BT1") (pin "1") (pinfunction "+_1") (pintype "passive"))
      (node (ref "U3") (pin "19") (pinfunction "VBAT_19") (pintype "power_in"))
    )
    (net (code "95") (name "VCC") (class "Default")
      (node (ref "C25") (pin "1") (pintype "passive"))
      (node (ref "C27") (pin "1") (pintype "passive"))
      (node (ref "J3") (pin "1") (pinfunction "1_1") (pintype "passive"))
      (node (ref "P1") (pin "15") (pinfunction "15_15") (pintype "passive"))
      (node (ref "P1") (pin "2") (pinfunction "2_2") (pintype "passive"))
      (node (ref "R36") (pin "CW") (pinfunction "+_CW") (pintype "passive"))
      (node (ref "U2") (pin "3") (pinfunction "VIN_3") (pintype "power_in"))
    )
    (net (code "96") (name "unconnected-(J3-Pad3)") (class "Default")
      (node (ref "J3") (pin "3") (pinfunction "3_3") (pintype "passive"))
    )
    (net (code "97") (name "unconnected-(P1-Pad7)") (class "Default")
      (node (ref "P1") (pin "7") (pinfunction "7_7") (pintype "passive"))
    )
    (net (code "98") (name "unconnected-(P1-Pad8)") (class "Default")
      (node (ref "P1") (pin "8") (pinfunction "8_8") (pintype "passive"))
    )
    (net (code "99") (name "unconnected-(P1-Pad9)") (class "Default")
      (node (ref "P1") (pin "9") (pinfunction "9_9") (pintype "passive"))
    )
    (net (code "100") (name "unconnected-(P1-Pad10)") (class "Default")
      (node (ref "P1") (pin "10") (pinfunction "10_10") (pintype "passive"))
    )
    (net (code "101") (name "unconnected-(U3A-NC-Pad13)") (class "Default")
      (node (ref "U3") (pin "13") (pinfunction "NC_13") (pintype "passive"))
    )
    (net (code "102") (name "unconnected-(U3A-RTCK-Pad100)") (class "Default")
      (node (ref "U3") (pin "100") (pinfunction "RTCK_100") (pintype "output"))
    )
  )
)
